# M_2_NVME_CON.net
KiCad netlist of a schematic drawn in Altium Designer
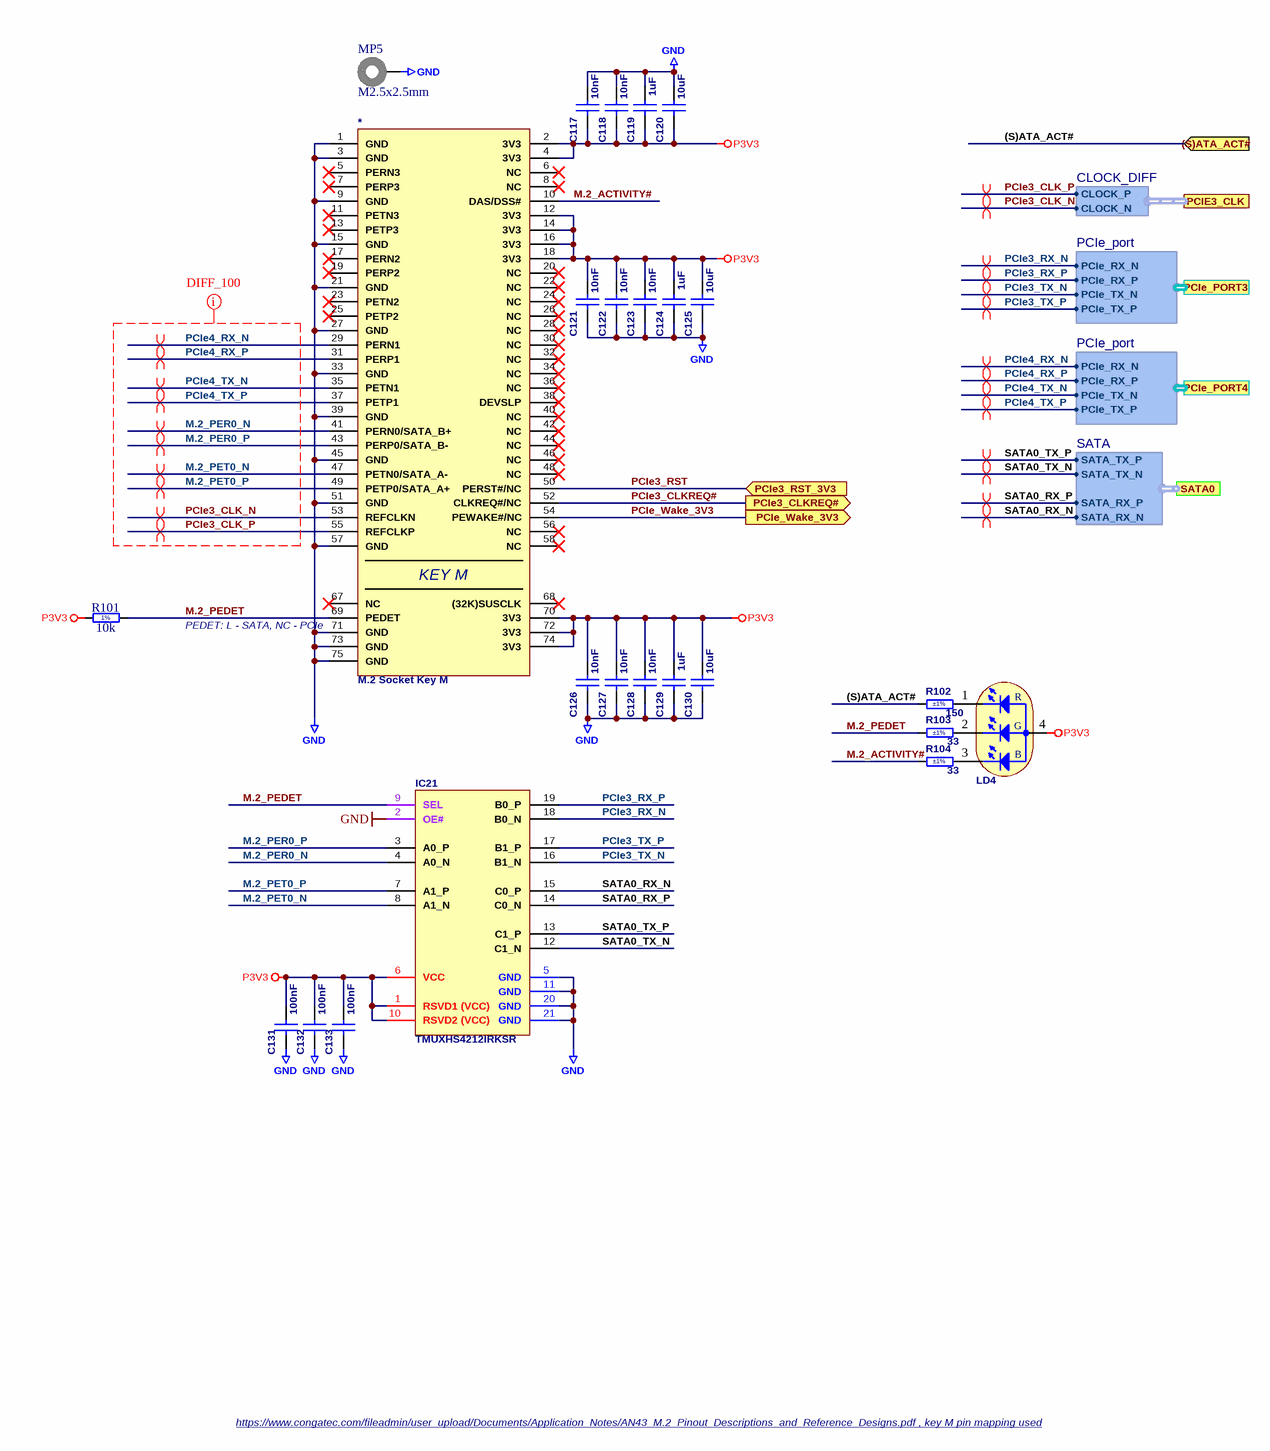
[diagram p0: M.2_NVME_CON.SchDoc]

(export (version "E")
  (design (tool "Eeschema 10.0.6"))
  (components
    (comp (ref "*")
      (value "M.2 Socket Key M")
      (footprint "FP-1-2199230-6-MFG")
      (libsource (lib "Kasil_DIOT_x86_board") (part "M.2 Socket Key M"))
    )
    (comp (ref "C117")
      (value "10nF")
      (footprint "CAPC1005X55N")
      (description "Non-polarised capacitor")
      (fields
        (field (name "PART NUMBER") "CC0402_10NF_16V_10%_X7R")
        (field (name "VOLTAGE") "16V")
        (field (name "AUTHOR") "CERN DEM JLC")
      )
      (libsource (lib "Capacitors") (part "Capacitor - non polarized"))
    )
    (comp (ref "C118")
      (value "10nF")
      (footprint "CAPC1005X55N")
      (description "Non-polarised capacitor")
      (fields
        (field (name "PART NUMBER") "CC0402_10NF_16V_10%_X7R")
        (field (name "VOLTAGE") "16V")
        (field (name "AUTHOR") "CERN DEM JLC")
      )
      (libsource (lib "Capacitors") (part "Capacitor - non polarized"))
    )
    (comp (ref "C119")
      (value "1uF")
      (footprint "CAPC1005X55N")
      (description "Non-polarised capacitor")
      (fields
        (field (name "PART NUMBER") "CC0402_1UF_16V_10%_X5R")
        (field (name "VOLTAGE") "16V")
        (field (name "AUTHOR") "CERN DEM JLC")
      )
      (libsource (lib "Capacitors") (part "Capacitor - non polarized"))
    )
    (comp (ref "C120")
      (value "10uF")
      (footprint "CAPC1608X80N")
      (description "Non-polarised capacitor")
      (fields
        (field (name "PART NUMBER") "CC0603_10UF_16V_20%_X5R")
        (field (name "VOLTAGE") "16V")
        (field (name "AUTHOR") "CERN DEM MR")
      )
      (libsource (lib "Capacitors") (part "Capacitor - non polarized"))
    )
    (comp (ref "C121")
      (value "10nF")
      (footprint "CAPC1005X55N")
      (description "Non-polarised capacitor")
      (fields
        (field (name "PART NUMBER") "CC0402_10NF_16V_10%_X7R")
        (field (name "VOLTAGE") "16V")
        (field (name "AUTHOR") "CERN DEM JLC")
      )
      (libsource (lib "Capacitors") (part "Capacitor - non polarized"))
    )
    (comp (ref "C122")
      (value "10nF")
      (footprint "CAPC1005X55N")
      (description "Non-polarised capacitor")
      (fields
        (field (name "PART NUMBER") "CC0402_10NF_16V_10%_X7R")
        (field (name "VOLTAGE") "16V")
        (field (name "AUTHOR") "CERN DEM JLC")
      )
      (libsource (lib "Capacitors") (part "Capacitor - non polarized"))
    )
    (comp (ref "C123")
      (value "10nF")
      (footprint "CAPC1005X55N")
      (description "Non-polarised capacitor")
      (fields
        (field (name "PART NUMBER") "CC0402_10NF_16V_10%_X7R")
        (field (name "VOLTAGE") "16V")
        (field (name "AUTHOR") "CERN DEM JLC")
      )
      (libsource (lib "Capacitors") (part "Capacitor - non polarized"))
    )
    (comp (ref "C124")
      (value "1uF")
      (footprint "CAPC1005X55N")
      (description "Non-polarised capacitor")
      (fields
        (field (name "PART NUMBER") "CC0402_1UF_16V_10%_X5R")
        (field (name "VOLTAGE") "16V")
        (field (name "AUTHOR") "CERN DEM JLC")
      )
      (libsource (lib "Capacitors") (part "Capacitor - non polarized"))
    )
    (comp (ref "C125")
      (value "10uF")
      (footprint "CAPC1608X80N")
      (description "Non-polarised capacitor")
      (fields
        (field (name "PART NUMBER") "CC0603_10UF_16V_20%_X5R")
        (field (name "VOLTAGE") "16V")
        (field (name "AUTHOR") "CERN DEM MR")
      )
      (libsource (lib "Capacitors") (part "Capacitor - non polarized"))
    )
    (comp (ref "C126")
      (value "10nF")
      (footprint "CAPC1005X55N")
      (description "Non-polarised capacitor")
      (fields
        (field (name "PART NUMBER") "CC0402_10NF_16V_10%_X7R")
        (field (name "VOLTAGE") "16V")
        (field (name "AUTHOR") "CERN DEM JLC")
      )
      (libsource (lib "Capacitors") (part "Capacitor - non polarized"))
    )
    (comp (ref "C127")
      (value "10nF")
      (footprint "CAPC1005X55N")
      (description "Non-polarised capacitor")
      (fields
        (field (name "PART NUMBER") "CC0402_10NF_16V_10%_X7R")
        (field (name "VOLTAGE") "16V")
        (field (name "AUTHOR") "CERN DEM JLC")
      )
      (libsource (lib "Capacitors") (part "Capacitor - non polarized"))
    )
    (comp (ref "C128")
      (value "10nF")
      (footprint "CAPC1005X55N")
      (description "Non-polarised capacitor")
      (fields
        (field (name "PART NUMBER") "CC0402_10NF_16V_10%_X7R")
        (field (name "VOLTAGE") "16V")
        (field (name "AUTHOR") "CERN DEM JLC")
      )
      (libsource (lib "Capacitors") (part "Capacitor - non polarized"))
    )
    (comp (ref "C129")
      (value "1uF")
      (footprint "CAPC1005X55N")
      (description "Non-polarised capacitor")
      (fields
        (field (name "PART NUMBER") "CC0402_1UF_16V_10%_X5R")
        (field (name "VOLTAGE") "16V")
        (field (name "AUTHOR") "CERN DEM JLC")
      )
      (libsource (lib "Capacitors") (part "Capacitor - non polarized"))
    )
    (comp (ref "C130")
      (value "10uF")
      (footprint "CAPC1608X80N")
      (description "Non-polarised capacitor")
      (fields
        (field (name "PART NUMBER") "CC0603_10UF_16V_20%_X5R")
        (field (name "VOLTAGE") "16V")
        (field (name "AUTHOR") "CERN DEM MR")
      )
      (libsource (lib "Capacitors") (part "Capacitor - non polarized"))
    )
    (comp (ref "C131")
      (value "100nF")
      (footprint "CAPC1005X55N")
      (description "Non-polarised capacitor")
      (fields
        (field (name "PART NUMBER") "CC0402_100NF_16V_10%_X7R")
        (field (name "VOLTAGE") "16V")
        (field (name "AUTHOR") "CERN DEM JLC")
      )
      (libsource (lib "Capacitors") (part "Capacitor - non polarized"))
    )
    (comp (ref "C132")
      (value "100nF")
      (footprint "CAPC1005X55N")
      (description "Non-polarised capacitor")
      (fields
        (field (name "PART NUMBER") "CC0402_100NF_16V_10%_X7R")
        (field (name "VOLTAGE") "16V")
        (field (name "AUTHOR") "CERN DEM JLC")
      )
      (libsource (lib "Capacitors") (part "Capacitor - non polarized"))
    )
    (comp (ref "C133")
      (value "100nF")
      (footprint "CAPC1005X55N")
      (description "Non-polarised capacitor")
      (fields
        (field (name "PART NUMBER") "CC0402_100NF_16V_10%_X7R")
        (field (name "VOLTAGE") "16V")
        (field (name "AUTHOR") "CERN DEM JLC")
      )
      (libsource (lib "Capacitors") (part "Capacitor - non polarized"))
    )
    (comp (ref "IC21")
      (value "TMUXHS4212IRKSR")
      (footprint "TI_RKS0020A")
      (description "Two-Channel Differential 2:1 MUX or 1:2 Demux")
      (libsource (lib "Kasil_DIOT_x86_board") (part "TMUXHS4212"))
    )
    (comp (ref "LD4")
      (value "Red/Green/Blue")
      (footprint "LED_OPTEK_OVSRRGBCC3_a")
      (description "Right Angle Tricolor (RGB) Surface Mount LED, Body 3.2x1mm")
      (fields
        (field (name "PART NUMBER") "LED_OPTEK_OVSRRGBCC3_a")
        (field (name "MANUFACTURER") "OPTEK / TT ELECTRONICS")
        (field (name "AUTHOR") "CERN DEM JLC")
      )
      (libsource (lib "ICs And Semiconductors") (part "LED_OPTEK_OVSRRGBCC3"))
    )
    (comp (ref "MP5")
      (value "M2.5x2.5mm")
      (footprint "9774025151")
      (description "WA-SMSI SMT Steel Spacer, internal Thread, OD 5.1mm, M2.5x2.5mm")
      (fields
        (field (name "MANUFACTURER PART NUMBER") "9774025151")
        (field (name "MANUFACTURER") "Wurth Elektronik")
      )
      (libsource (lib "Altium_WA-SMSI (rev21a)") (part "9774025151"))
    )
    (comp (ref "R101")
      (value "10k")
      (footprint "RESC1005X40N")
      (description "Resistor - 1%")
      (fields
        (field (name "PART NUMBER") "R0402_10K_1%_0.0625W_100PPM")
        (field (name "POWER") "0.0625W")
        (field (name "AUTHOR") "CERN DEM JLC")
      )
      (libsource (lib "Resistors") (part "Resistor - 1%"))
    )
    (comp (ref "R102")
      (value "150")
      (footprint "RESC1005X40N")
      (description "Resistor - 1%")
      (fields
        (field (name "TOLERANCE") "±1%")
        (field (name "PART NUMBER") "R0402_150R_1%_0.0625W_100PPM")
        (field (name "POWER") "0.0625W")
        (field (name "AUTHOR") "CERN DEM JLC")
      )
      (libsource (lib "Resistors") (part "Resistor - 1%"))
    )
    (comp (ref "R103")
      (value "33")
      (footprint "RESC1005X40N")
      (description "Resistor - 1%")
      (fields
        (field (name "TOLERANCE") "±1%")
        (field (name "PART NUMBER") "R0402_33R_1%_0.0625W_100PPM")
        (field (name "POWER") "0.0625W")
        (field (name "AUTHOR") "CERN DEM JLC")
      )
      (libsource (lib "Resistors") (part "Resistor - 1%"))
    )
    (comp (ref "R104")
      (value "33")
      (footprint "RESC1005X40N")
      (description "Resistor - 1%")
      (fields
        (field (name "TOLERANCE") "±1%")
        (field (name "PART NUMBER") "R0402_33R_1%_0.0625W_100PPM")
        (field (name "POWER") "0.0625W")
        (field (name "AUTHOR") "CERN DEM JLC")
      )
      (libsource (lib "Resistors") (part "Resistor - 1%"))
    )
  )
  (nets
    (net (code "4") (name "/(S)ATA_ACT#") (class "Default")
      (node (ref "R102") (pin "1") (pinfunction "1_1") (pintype "passive"))
    )
    (net (code "5") (name "/M.2_ACTIVITY#") (class "Default")
      (node (ref "*") (pin "10") (pinfunction "DAS/DSS#_10") (pintype "passive"))
      (node (ref "R104") (pin "1") (pinfunction "1_1") (pintype "passive"))
    )
    (net (code "6") (name "/M.2_PEDET") (class "Default")
      (node (ref "*") (pin "69") (pinfunction "PEDET_69") (pintype "passive"))
      (node (ref "IC21") (pin "9") (pinfunction "SEL_9") (pintype "passive"))
      (node (ref "R101") (pin "2") (pinfunction "2_2") (pintype "passive"))
      (node (ref "R103") (pin "1") (pinfunction "1_1") (pintype "passive"))
    )
    (net (code "7") (name "/M.2_PER0_N") (class "Default")
      (node (ref "*") (pin "41") (pinfunction "PERN0/SATA_B+_41") (pintype "passive"))
      (node (ref "IC21") (pin "4") (pinfunction "A0_N_4") (pintype "passive"))
    )
    (net (code "8") (name "/M.2_PER0_P") (class "Default")
      (node (ref "*") (pin "43") (pinfunction "PERP0/SATA_B-_43") (pintype "passive"))
      (node (ref "IC21") (pin "3") (pinfunction "A0_P_3") (pintype "passive"))
    )
    (net (code "9") (name "/M.2_PET0_N") (class "Default")
      (node (ref "*") (pin "47") (pinfunction "PETN0/SATA_A-_47") (pintype "passive"))
      (node (ref "IC21") (pin "8") (pinfunction "A1_N_8") (pintype "passive"))
    )
    (net (code "10") (name "/M.2_PET0_P") (class "Default")
      (node (ref "*") (pin "49") (pinfunction "PETP0/SATA_A+_49") (pintype "passive"))
      (node (ref "IC21") (pin "7") (pinfunction "A1_P_7") (pintype "passive"))
    )
    (net (code "11") (name "/PCIe3_CLKREQ#") (class "Default")
      (node (ref "*") (pin "52") (pinfunction "CLKREQ#/NC_52") (pintype "passive"))
    )
    (net (code "12") (name "/PCIe3_CLK_N") (class "Default")
      (node (ref "*") (pin "53") (pinfunction "REFCLKN_53") (pintype "passive"))
    )
    (net (code "13") (name "/PCIe3_CLK_P") (class "Default")
      (node (ref "*") (pin "55") (pinfunction "REFCLKP_55") (pintype "passive"))
    )
    (net (code "14") (name "/PCIe3_RST") (class "Default")
      (node (ref "*") (pin "50") (pinfunction "PERST#/NC_50") (pintype "passive"))
    )
    (net (code "15") (name "/PCIe3_RX_N") (class "Default")
      (node (ref "IC21") (pin "18") (pinfunction "B0_N_18") (pintype "passive"))
    )
    (net (code "16") (name "/PCIe3_RX_P") (class "Default")
      (node (ref "IC21") (pin "19") (pinfunction "B0_P_19") (pintype "passive"))
    )
    (net (code "17") (name "/PCIe3_TX_N") (class "Default")
      (node (ref "IC21") (pin "16") (pinfunction "B1_N_16") (pintype "passive"))
    )
    (net (code "18") (name "/PCIe3_TX_P") (class "Default")
      (node (ref "IC21") (pin "17") (pinfunction "B1_P_17") (pintype "passive"))
    )
    (net (code "19") (name "/PCIe4_RX_N") (class "Default")
      (node (ref "*") (pin "29") (pinfunction "PERN1_29") (pintype "passive"))
    )
    (net (code "20") (name "/PCIe4_RX_P") (class "Default")
      (node (ref "*") (pin "31") (pinfunction "PERP1_31") (pintype "passive"))
    )
    (net (code "21") (name "/PCIe4_TX_N") (class "Default")
      (node (ref "*") (pin "35") (pinfunction "PETN1_35") (pintype "passive"))
    )
    (net (code "22") (name "/PCIe4_TX_P") (class "Default")
      (node (ref "*") (pin "37") (pinfunction "PETP1_37") (pintype "passive"))
    )
    (net (code "23") (name "/PCIe_Wake_3V3") (class "Default")
      (node (ref "*") (pin "54") (pinfunction "PEWAKE#/NC_54") (pintype "passive"))
    )
    (net (code "24") (name "/SATA0_RX_N") (class "Default")
      (node (ref "IC21") (pin "15") (pinfunction "C0_P_15") (pintype "passive"))
    )
    (net (code "25") (name "/SATA0_RX_P") (class "Default")
      (node (ref "IC21") (pin "14") (pinfunction "C0_N_14") (pintype "passive"))
    )
    (net (code "26") (name "/SATA0_TX_N") (class "Default")
      (node (ref "IC21") (pin "12") (pinfunction "C1_N_12") (pintype "passive"))
    )
    (net (code "27") (name "/SATA0_TX_P") (class "Default")
      (node (ref "IC21") (pin "13") (pinfunction "C1_P_13") (pintype "passive"))
    )
    (net (code "31") (name "GND") (class "Default")
      (node (ref "*") (pin "1") (pinfunction "GND_1") (pintype "passive"))
      (node (ref "*") (pin "15") (pinfunction "GND_15") (pintype "passive"))
      (node (ref "*") (pin "21") (pinfunction "GND_21") (pintype "passive"))
      (node (ref "*") (pin "27") (pinfunction "GND_27") (pintype "passive"))
      (node (ref "*") (pin "3") (pinfunction "GND_3") (pintype "passive"))
      (node (ref "*") (pin "33") (pinfunction "GND_33") (pintype "passive"))
      (node (ref "*") (pin "39") (pinfunction "GND_39") (pintype "passive"))
      (node (ref "*") (pin "45") (pinfunction "GND_45") (pintype "passive"))
      (node (ref "*") (pin "51") (pinfunction "GND_51") (pintype "passive"))
      (node (ref "*") (pin "57") (pinfunction "GND_57") (pintype "passive"))
      (node (ref "*") (pin "71") (pinfunction "GND_71") (pintype "passive"))
      (node (ref "*") (pin "73") (pinfunction "GND_73") (pintype "passive"))
      (node (ref "*") (pin "75") (pinfunction "GND_75") (pintype "passive"))
      (node (ref "*") (pin "9") (pinfunction "GND_9") (pintype "passive"))
      (node (ref "C117") (pin "2") (pinfunction "2_2") (pintype "passive"))
      (node (ref "C118") (pin "2") (pinfunction "2_2") (pintype "passive"))
      (node (ref "C119") (pin "2") (pinfunction "2_2") (pintype "passive"))
      (node (ref "C120") (pin "2") (pinfunction "2_2") (pintype "passive"))
      (node (ref "C121") (pin "1") (pinfunction "1_1") (pintype "passive"))
      (node (ref "C122") (pin "1") (pinfunction "1_1") (pintype "passive"))
      (node (ref "C123") (pin "1") (pinfunction "1_1") (pintype "passive"))
      (node (ref "C124") (pin "1") (pinfunction "1_1") (pintype "passive"))
      (node (ref "C125") (pin "1") (pinfunction "1_1") (pintype "passive"))
      (node (ref "C126") (pin "1") (pinfunction "1_1") (pintype "passive"))
      (node (ref "C127") (pin "1") (pinfunction "1_1") (pintype "passive"))
      (node (ref "C128") (pin "1") (pinfunction "1_1") (pintype "passive"))
      (node (ref "C129") (pin "1") (pinfunction "1_1") (pintype "passive"))
      (node (ref "C130") (pin "1") (pinfunction "1_1") (pintype "passive"))
      (node (ref "C131") (pin "1") (pinfunction "1_1") (pintype "passive"))
      (node (ref "C132") (pin "1") (pinfunction "1_1") (pintype "passive"))
      (node (ref "C133") (pin "1") (pinfunction "1_1") (pintype "passive"))
      (node (ref "IC21") (pin "11") (pinfunction "GND_11") (pintype "passive"))
      (node (ref "IC21") (pin "2") (pinfunction "OE#_2") (pintype "passive"))
      (node (ref "IC21") (pin "20") (pinfunction "GND_20") (pintype "passive"))
      (node (ref "IC21") (pin "21") (pinfunction "GND_21") (pintype "passive"))
      (node (ref "IC21") (pin "5") (pinfunction "GND_5") (pintype "passive"))
      (node (ref "MP5") (pin "1") (pinfunction "1_1") (pintype "passive"))
    )
    (net (code "32") (name "Net-(LD4-AB)") (class "Default")
      (node (ref "LD4") (pin "3") (pinfunction "AB_3") (pintype "passive"))
      (node (ref "R104") (pin "2") (pinfunction "2_2") (pintype "passive"))
    )
    (net (code "33") (name "Net-(LD4-AG)") (class "Default")
      (node (ref "LD4") (pin "2") (pinfunction "AG_2") (pintype "passive"))
      (node (ref "R103") (pin "2") (pinfunction "2_2") (pintype "passive"))
    )
    (net (code "34") (name "Net-(LD4-AR)") (class "Default")
      (node (ref "LD4") (pin "1") (pinfunction "AR_1") (pintype "passive"))
      (node (ref "R102") (pin "2") (pinfunction "2_2") (pintype "passive"))
    )
    (net (code "35") (name "P3V3") (class "Default")
      (node (ref "*") (pin "12") (pinfunction "3V3_12") (pintype "passive"))
      (node (ref "*") (pin "14") (pinfunction "3V3_14") (pintype "passive"))
      (node (ref "*") (pin "16") (pinfunction "3V3_16") (pintype "passive"))
      (node (ref "*") (pin "18") (pinfunction "3V3_18") (pintype "passive"))
      (node (ref "*") (pin "2") (pinfunction "3V3_2") (pintype "passive"))
      (node (ref "*") (pin "4") (pinfunction "3V3_4") (pintype "passive"))
      (node (ref "*") (pin "70") (pinfunction "3V3_70") (pintype "passive"))
      (node (ref "*") (pin "72") (pinfunction "3V3_72") (pintype "passive"))
      (node (ref "*") (pin "74") (pinfunction "3V3_74") (pintype "passive"))
      (node (ref "C117") (pin "1") (pinfunction "1_1") (pintype "passive"))
      (node (ref "C118") (pin "1") (pinfunction "1_1") (pintype "passive"))
      (node (ref "C119") (pin "1") (pinfunction "1_1") (pintype "passive"))
      (node (ref "C120") (pin "1") (pinfunction "1_1") (pintype "passive"))
      (node (ref "C121") (pin "2") (pinfunction "2_2") (pintype "passive"))
      (node (ref "C122") (pin "2") (pinfunction "2_2") (pintype "passive"))
      (node (ref "C123") (pin "2") (pinfunction "2_2") (pintype "passive"))
      (node (ref "C124") (pin "2") (pinfunction "2_2") (pintype "passive"))
      (node (ref "C125") (pin "2") (pinfunction "2_2") (pintype "passive"))
      (node (ref "C126") (pin "2") (pinfunction "2_2") (pintype "passive"))
      (node (ref "C127") (pin "2") (pinfunction "2_2") (pintype "passive"))
      (node (ref "C128") (pin "2") (pinfunction "2_2") (pintype "passive"))
      (node (ref "C129") (pin "2") (pinfunction "2_2") (pintype "passive"))
      (node (ref "C130") (pin "2") (pinfunction "2_2") (pintype "passive"))
      (node (ref "C131") (pin "2") (pinfunction "2_2") (pintype "passive"))
      (node (ref "C132") (pin "2") (pinfunction "2_2") (pintype "passive"))
      (node (ref "C133") (pin "2") (pinfunction "2_2") (pintype "passive"))
      (node (ref "IC21") (pin "1") (pinfunction "RSVD1_(VCC)_1") (pintype "passive"))
      (node (ref "IC21") (pin "10") (pinfunction "RSVD2_(VCC)_10") (pintype "passive"))
      (node (ref "IC21") (pin "6") (pinfunction "VCC_6") (pintype "passive"))
      (node (ref "LD4") (pin "4") (pinfunction "CC_4") (pintype "passive"))
      (node (ref "R101") (pin "1") (pinfunction "1_1") (pintype "passive"))
    )
    (net (code "36") (name "unconnected-(*-(32K)SUSCLK-Pad68)") (class "Default")
      (node (ref "*") (pin "68") (pinfunction "(32K)SUSCLK_68") (pintype "passive+no_connect"))
    )
    (net (code "37") (name "unconnected-(*-DEVSLP-Pad38)") (class "Default")
      (node (ref "*") (pin "38") (pinfunction "DEVSLP_38") (pintype "passive+no_connect"))
    )
    (net (code "38") (name "unconnected-(*-NC-Pad6)") (class "Default")
      (node (ref "*") (pin "6") (pinfunction "NC_6") (pintype "passive+no_connect"))
    )
    (net (code "39") (name "unconnected-(*-NC-Pad8)") (class "Default")
      (node (ref "*") (pin "8") (pinfunction "NC_8") (pintype "passive+no_connect"))
    )
    (net (code "40") (name "unconnected-(*-NC-Pad20)") (class "Default")
      (node (ref "*") (pin "20") (pinfunction "NC_20") (pintype "passive+no_connect"))
    )
    (net (code "41") (name "unconnected-(*-NC-Pad22)") (class "Default")
      (node (ref "*") (pin "22") (pinfunction "NC_22") (pintype "passive+no_connect"))
    )
    (net (code "42") (name "unconnected-(*-NC-Pad24)") (class "Default")
      (node (ref "*") (pin "24") (pinfunction "NC_24") (pintype "passive+no_connect"))
    )
    (net (code "43") (name "unconnected-(*-NC-Pad26)") (class "Default")
      (node (ref "*") (pin "26") (pinfunction "NC_26") (pintype "passive+no_connect"))
    )
    (net (code "44") (name "unconnected-(*-NC-Pad28)") (class "Default")
      (node (ref "*") (pin "28") (pinfunction "NC_28") (pintype "passive+no_connect"))
    )
    (net (code "45") (name "unconnected-(*-NC-Pad30)") (class "Default")
      (node (ref "*") (pin "30") (pinfunction "NC_30") (pintype "passive+no_connect"))
    )
    (net (code "46") (name "unconnected-(*-NC-Pad32)") (class "Default")
      (node (ref "*") (pin "32") (pinfunction "NC_32") (pintype "passive+no_connect"))
    )
    (net (code "47") (name "unconnected-(*-NC-Pad34)") (class "Default")
      (node (ref "*") (pin "34") (pinfunction "NC_34") (pintype "passive+no_connect"))
    )
    (net (code "48") (name "unconnected-(*-NC-Pad36)") (class "Default")
      (node (ref "*") (pin "36") (pinfunction "NC_36") (pintype "passive+no_connect"))
    )
    (net (code "49") (name "unconnected-(*-NC-Pad40)") (class "Default")
      (node (ref "*") (pin "40") (pinfunction "NC_40") (pintype "passive+no_connect"))
    )
    (net (code "50") (name "unconnected-(*-NC-Pad42)") (class "Default")
      (node (ref "*") (pin "42") (pinfunction "NC_42") (pintype "passive+no_connect"))
    )
    (net (code "51") (name "unconnected-(*-NC-Pad44)") (class "Default")
      (node (ref "*") (pin "44") (pinfunction "NC_44") (pintype "passive+no_connect"))
    )
    (net (code "52") (name "unconnected-(*-NC-Pad46)") (class "Default")
      (node (ref "*") (pin "46") (pinfunction "NC_46") (pintype "passive+no_connect"))
    )
    (net (code "53") (name "unconnected-(*-NC-Pad48)") (class "Default")
      (node (ref "*") (pin "48") (pinfunction "NC_48") (pintype "passive+no_connect"))
    )
    (net (code "54") (name "unconnected-(*-NC-Pad56)") (class "Default")
      (node (ref "*") (pin "56") (pinfunction "NC_56") (pintype "passive+no_connect"))
    )
    (net (code "55") (name "unconnected-(*-NC-Pad58)") (class "Default")
      (node (ref "*") (pin "58") (pinfunction "NC_58") (pintype "passive+no_connect"))
    )
    (net (code "56") (name "unconnected-(*-NC-Pad67)") (class "Default")
      (node (ref "*") (pin "67") (pinfunction "NC_67") (pintype "passive+no_connect"))
    )
    (net (code "57") (name "unconnected-(*-PERN2-Pad17)") (class "Default")
      (node (ref "*") (pin "17") (pinfunction "PERN2_17") (pintype "passive+no_connect"))
    )
    (net (code "58") (name "unconnected-(*-PERN3-Pad5)") (class "Default")
      (node (ref "*") (pin "5") (pinfunction "PERN3_5") (pintype "passive+no_connect"))
    )
    (net (code "59") (name "unconnected-(*-PERP2-Pad19)") (class "Default")
      (node (ref "*") (pin "19") (pinfunction "PERP2_19") (pintype "passive+no_connect"))
    )
    (net (code "60") (name "unconnected-(*-PERP3-Pad7)") (class "Default")
      (node (ref "*") (pin "7") (pinfunction "PERP3_7") (pintype "passive+no_connect"))
    )
    (net (code "61") (name "unconnected-(*-PETN2-Pad23)") (class "Default")
      (node (ref "*") (pin "23") (pinfunction "PETN2_23") (pintype "passive+no_connect"))
    )
    (net (code "62") (name "unconnected-(*-PETN3-Pad11)") (class "Default")
      (node (ref "*") (pin "11") (pinfunction "PETN3_11") (pintype "passive+no_connect"))
    )
    (net (code "63") (name "unconnected-(*-PETP2-Pad25)") (class "Default")
      (node (ref "*") (pin "25") (pinfunction "PETP2_25") (pintype "passive+no_connect"))
    )
    (net (code "64") (name "unconnected-(*-PETP3-Pad13)") (class "Default")
      (node (ref "*") (pin "13") (pinfunction "PETP3_13") (pintype "passive+no_connect"))
    )
  )
)
